# Sheet2.net
KiCad netlist of a schematic drawn in Altium Designer
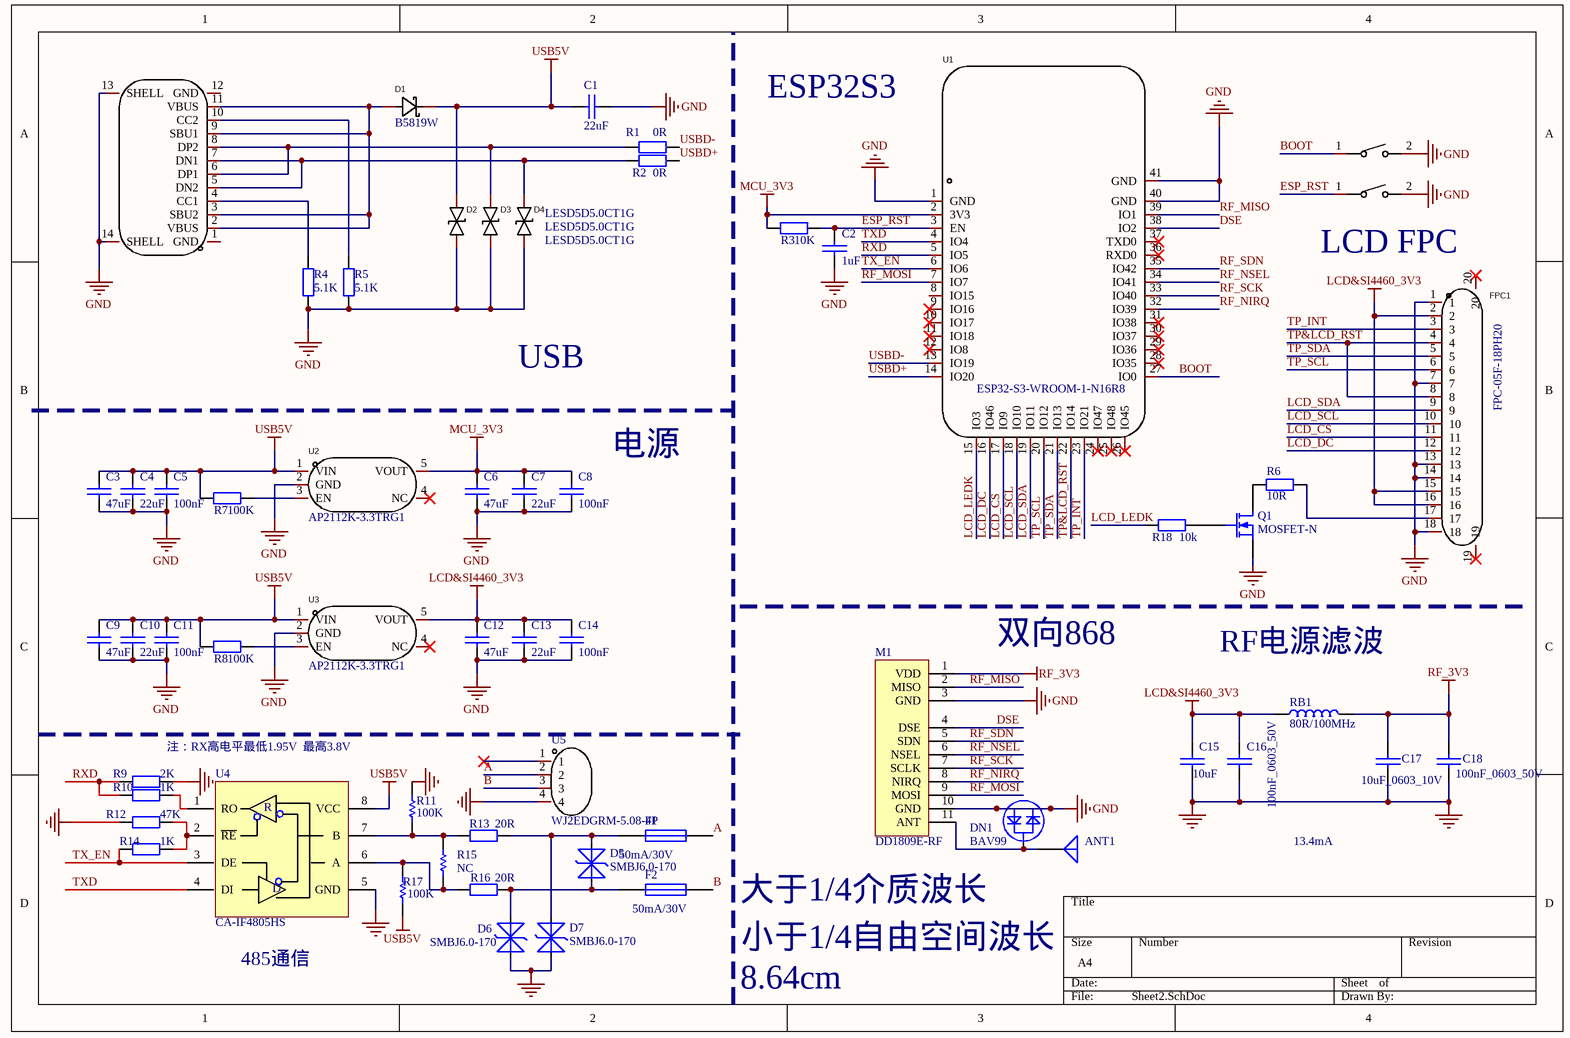
[diagram p0: Sheet2.SchDoc]

(export (version "E")
  (design (tool "Eeschema 10.0.6"))
  (components
    (comp (ref "ANT1")
      (value "~")
      (footprint "18AWG")
      (description "Generic Antenna")
      (fields (field (name "PUBLISHER") "Altium Limited"))
      (libsource (lib "原理图库") (part "Antenna"))
    )
    (comp (ref "C1")
      (value "22uF")
      (footprint "0603_C")
      (description "贴片电容")
      (libsource (lib "Schlib1") (part "CAP_SMT"))
    )
    (comp (ref "C2")
      (value "1uF")
      (footprint "0603_C")
      (description "贴片电容")
      (libsource (lib "Schlib1") (part "CAP_SMT"))
    )
    (comp (ref "C3")
      (value "47uF")
      (footprint "0603_C")
      (description "贴片电容")
      (libsource (lib "Schlib1") (part "CAP_SMT"))
    )
    (comp (ref "C4")
      (value "22uF")
      (footprint "0603_C")
      (description "贴片电容")
      (libsource (lib "Schlib1") (part "CAP_SMT"))
    )
    (comp (ref "C5")
      (value "100nF")
      (footprint "0603_C")
      (description "贴片电容")
      (libsource (lib "Schlib1") (part "CAP_SMT"))
    )
    (comp (ref "C6")
      (value "47uF")
      (footprint "0603_C")
      (description "贴片电容")
      (libsource (lib "Schlib1") (part "CAP_SMT"))
    )
    (comp (ref "C7")
      (value "22uF")
      (footprint "0603_C")
      (description "贴片电容")
      (libsource (lib "Schlib1") (part "CAP_SMT"))
    )
    (comp (ref "C8")
      (value "100nF")
      (footprint "0603_C")
      (description "贴片电容")
      (libsource (lib "Schlib1") (part "CAP_SMT"))
    )
    (comp (ref "C9")
      (value "47uF")
      (footprint "0603_C")
      (description "贴片电容")
      (libsource (lib "Schlib1") (part "CAP_SMT"))
    )
    (comp (ref "C10")
      (value "22uF")
      (footprint "0603_C")
      (description "贴片电容")
      (libsource (lib "Schlib1") (part "CAP_SMT"))
    )
    (comp (ref "C11")
      (value "100nF")
      (footprint "0603_C")
      (description "贴片电容")
      (libsource (lib "Schlib1") (part "CAP_SMT"))
    )
    (comp (ref "C12")
      (value "47uF")
      (footprint "0603_C")
      (description "贴片电容")
      (libsource (lib "Schlib1") (part "CAP_SMT"))
    )
    (comp (ref "C13")
      (value "22uF")
      (footprint "0603_C")
      (description "贴片电容")
      (libsource (lib "Schlib1") (part "CAP_SMT"))
    )
    (comp (ref "C14")
      (value "100nF")
      (footprint "0603_C")
      (description "贴片电容")
      (libsource (lib "Schlib1") (part "CAP_SMT"))
    )
    (comp (ref "C15")
      (value "10uF")
      (footprint "0603_C")
      (description "瓷片电容 X5R-0603-10V-10uF/C-±10%")
      (fields (field (name "Comment") "10uF_0603_10V"))
      (libsource (lib "mine") (part "10uF_0603_10V"))
    )
    (comp (ref "C16")
      (value "100nF_0603_50V")
      (footprint "0603_C")
      (description "电容 瓷片 X7R-0603-50V-0.1uF/C-±10%")
      (libsource (lib "mine") (part "100nF_0603_50V"))
    )
    (comp (ref "C17")
      (value "10uF_0603_10V")
      (footprint "0603_C")
      (description "瓷片电容 X5R-0603-10V-10uF/C-±10%")
      (libsource (lib "mine") (part "10uF_0603_10V"))
    )
    (comp (ref "C18")
      (value "100nF_0603_50V")
      (footprint "0603_C")
      (description "电容 瓷片 X7R-0603-50V-0.1uF/C-±10%")
      (libsource (lib "mine") (part "100nF_0603_50V"))
    )
    (comp (ref "D1")
      (value "B5819W")
      (footprint "SOD-123F_L2.7-W1.6-LS3.8-RD-1")
      (fields (field (name "MANUFACTURER") "GOODWORK(固得沃克)"))
      (libsource (lib "Schlib1") (part "B5819W"))
    )
    (comp (ref "D2")
      (value "LESD5D5.0CT1G")
      (footprint "SOD-523_L1.2-W0.8-LS1.6-BI")
      (fields (field (name "MANUFACTURER") "LRC(乐山无线电)"))
      (libsource (lib "Schlib1") (part "LESD5D5.0CT1G"))
    )
    (comp (ref "D3")
      (value "LESD5D5.0CT1G")
      (footprint "SOD-523_L1.2-W0.8-LS1.6-BI")
      (fields (field (name "MANUFACTURER") "LRC(乐山无线电)"))
      (libsource (lib "Schlib1") (part "LESD5D5.0CT1G"))
    )
    (comp (ref "D4")
      (value "LESD5D5.0CT1G")
      (footprint "SOD-523_L1.2-W0.8-LS1.6-BI")
      (fields (field (name "MANUFACTURER") "LRC(乐山无线电)"))
      (libsource (lib "Schlib1") (part "LESD5D5.0CT1G"))
    )
    (comp (ref "D5")
      (value "SMBJ6.0-170")
      (footprint "SMB(DO-214AA) - TVS")
      (description "TVS")
      (libsource (lib "Schlib1") (part "TVS"))
    )
    (comp (ref "D6")
      (value "SMBJ6.0-170")
      (footprint "SMB(DO-214AA) - TVS")
      (description "TVS")
      (libsource (lib "Schlib1") (part "TVS"))
    )
    (comp (ref "D7")
      (value "SMBJ6.0-170")
      (footprint "SMB(DO-214AA) - TVS")
      (description "TVS")
      (libsource (lib "Schlib1") (part "TVS"))
    )
    (comp (ref "DN1") (value "BAV99") (footprint "SOT-23(SOT-23-3)") (libsource (lib "Ruan") (part "BAV99")))
    (comp (ref "F1")
      (value "贴片自恢复保险丝 1812 0.1A 60V")
      (footprint "1206_R")
      (description "Fuse")
      (fields (field (name "ALTIUM_UNNAMED_1") "50mA/30V") (field (name "PUBLISHER") "Altium Limited"))
      (libsource (lib "*") (part "Fuse 1"))
    )
    (comp (ref "F2")
      (value "贴片自恢复保险丝 1812 0.1A 60V")
      (footprint "1206_R")
      (description "Fuse")
      (fields (field (name "ALTIUM_UNNAMED_1") "50mA/30V") (field (name "PUBLISHER") "Altium Limited"))
      (libsource (lib "*") (part "Fuse 1"))
    )
    (comp (ref "FPC1")
      (value "FPC-05F-18PH20")
      (footprint "FPC-SMD_18P-P0.50_FPC-05F-18PH20")
      (fields (field (name "MANUFACTURER") "XUNPU(讯普)"))
      (libsource (lib "Schlib1") (part "FPC-05F-18PH20"))
    )
    (comp (ref "M1")
      (value "DD1809E-RF")
      (footprint "DD1809(E)-RF-平")
      (description "平插")
      (libsource (lib "Ruan") (part "DD1809E-RF"))
    )
    (comp (ref "Q1")
      (value "MOSFET-N")
      (footprint "SOT-23(SOT-23-3)")
      (description "N-Channel MOSFET")
      (libsource (lib "Schlib1") (part "MOSFET-N"))
    )
    (comp (ref "R1")
      (value "0R")
      (footprint "0603_R")
      (description "Resistor")
      (fields (field (name "PUBLISHER") "Altium Limited"))
      (libsource (lib "Schlib1") (part "RES"))
    )
    (comp (ref "R2")
      (value "0R")
      (footprint "0603_R")
      (description "Resistor")
      (fields (field (name "PUBLISHER") "Altium Limited"))
      (libsource (lib "Schlib1") (part "RES"))
    )
    (comp (ref "R3")
      (value "10K")
      (footprint "0603_R")
      (description "Resistor")
      (fields (field (name "Comment") "0R") (field (name "PUBLISHER") "Altium Limited"))
      (libsource (lib "Schlib1") (part "RES"))
    )
    (comp (ref "R4")
      (value "5.1K")
      (footprint "0603_R")
      (description "Resistor")
      (fields (field (name "PUBLISHER") "Altium Limited"))
      (libsource (lib "") (part "RES_1"))
    )
    (comp (ref "R5")
      (value "5.1K")
      (footprint "0603_R")
      (description "Resistor")
      (fields (field (name "PUBLISHER") "Altium Limited"))
      (libsource (lib "") (part "RES_1"))
    )
    (comp (ref "R6")
      (value "10R")
      (footprint "0603_R")
      (description "Resistor")
      (fields (field (name "Comment") "0R") (field (name "PUBLISHER") "Altium Limited"))
      (libsource (lib "Schlib1") (part "RES"))
    )
    (comp (ref "R7")
      (value "100K")
      (footprint "0603_R")
      (description "Resistor")
      (fields (field (name "PUBLISHER") "Altium Limited"))
      (libsource (lib "Schlib1") (part "RES"))
    )
    (comp (ref "R8")
      (value "100K")
      (footprint "0603_R")
      (description "Resistor")
      (fields (field (name "PUBLISHER") "Altium Limited"))
      (libsource (lib "Schlib1") (part "RES"))
    )
    (comp (ref "R9")
      (value "2K")
      (footprint "0603_R")
      (description "Resistor")
      (fields (field (name "PUBLISHER") "Altium Limited"))
      (libsource (lib "") (part "Res2_2"))
    )
    (comp (ref "R10")
      (value "1K")
      (footprint "0603_R")
      (description "Resistor")
      (fields (field (name "PUBLISHER") "Altium Limited"))
      (libsource (lib "*") (part "Res2"))
    )
    (comp (ref "R11")
      (value "100K")
      (footprint "0603_R")
      (description "Resistor")
      (fields (field (name "PUBLISHER") "Altium Limited"))
      (libsource (lib "*") (part "Res1"))
    )
    (comp (ref "R12")
      (value "47K")
      (footprint "0603_R")
      (description "Resistor")
      (fields (field (name "PUBLISHER") "Altium Limited"))
      (libsource (lib "*") (part "Res2"))
    )
    (comp (ref "R13")
      (value "20R")
      (footprint "0603_R")
      (description "Resistor")
      (fields (field (name "PUBLISHER") "Altium Limited"))
      (libsource (lib "") (part "Res2_1"))
    )
    (comp (ref "R14")
      (value "1K")
      (footprint "0603_R")
      (description "Resistor")
      (fields (field (name "PUBLISHER") "Altium Limited"))
      (libsource (lib "*") (part "Res2"))
    )
    (comp (ref "R15")
      (value "NC")
      (footprint "0603_R")
      (description "Resistor")
      (fields (field (name "PUBLISHER") "Altium Limited"))
      (libsource (lib "*") (part "Res1"))
    )
    (comp (ref "R16")
      (value "20R")
      (footprint "0603_R")
      (description "Resistor")
      (fields (field (name "PUBLISHER") "Altium Limited"))
      (libsource (lib "") (part "Res2_1"))
    )
    (comp (ref "R17")
      (value "100K")
      (footprint "0603_R")
      (description "Resistor")
      (fields (field (name "PUBLISHER") "Altium Limited"))
      (libsource (lib "*") (part "Res1"))
    )
    (comp (ref "R18")
      (value "10k")
      (footprint "0603_R")
      (description "Resistor")
      (fields (field (name "Comment") "0R") (field (name "PUBLISHER") "Altium Limited"))
      (libsource (lib "Schlib1") (part "RES"))
    )
    (comp (ref "RB1")
      (value "80R/100MHz")
      (footprint "0603_R")
      (description "磁珠 80R/100MHZ 贴片0603")
      (fields (field (name "Comment") "80R/100MHz_0603"))
      (libsource (lib "mine") (part "80R/100MHz_0603"))
    )
    (comp (ref "SW1")
      (value "TS-1088-AR02016")
      (footprint "SW-SMD_L3.9-W3.0-P4.45")
      (fields (field (name "MANUFACTURER") "XUNPU(讯普)"))
      (libsource (lib "Schlib1") (part "KEY"))
    )
    (comp (ref "SW2")
      (value "TS-1088-AR02016")
      (footprint "SW-SMD_L3.9-W3.0-P4.45")
      (fields (field (name "MANUFACTURER") "XUNPU(讯普)"))
      (libsource (lib "Schlib1") (part "KEY"))
    )
    (comp (ref "U1")
      (value "ESP32-S3-WROOM-1-N16R8")
      (footprint "WIRELM-SMD_ESP32-S3-WROOM-1")
      (fields (field (name "MANUFACTURER") "ESPRESSIF(乐鑫)"))
      (libsource (lib "Schlib1") (part "ESP32-S3-WROOM-1-N16R8"))
    )
    (comp (ref "U2")
      (value "AP2112K-3.3TRG1")
      (footprint "SOT-25-5_L2.9-W1.6-P0.95-LS2.8-BL")
      (fields (field (name "MANUFACTURER") "DIODES(美台)"))
      (libsource (lib "Schlib1") (part "AP2112K-3.3TRG1"))
    )
    (comp (ref "U3")
      (value "AP2112K-3.3TRG1")
      (footprint "SOT-25-5_L2.9-W1.6-P0.95-LS2.8-BL")
      (fields (field (name "MANUFACTURER") "DIODES(美台)"))
      (libsource (lib "Schlib1") (part "AP2112K-3.3TRG1"))
    )
    (comp (ref "U4")
      (value "CA-IF4805HS")
      (footprint "SOP8")
      (description "MAX485E")
      (libsource (lib "N IC-GRC") (part "MAX485E"))
    )
    (comp (ref "U5")
      (value "WJ2EDGRM-5.08-4P")
      (footprint "CONN-TH_4P-P5.08_WJ2EDGRM-5.08-4P-14-00A")
      (description "连接器类型:板端/插座-闭口;间距:5.08mm;排数:1;每排PIN数:4;安装方式:弯针;颜色:绿色;固定方式:螺丝固定;")
      (fields (field (name "MANUFACTURER") "KANGNEX(康奈克斯电气)") (field (name "NAME") "WJ2EDGRM-5.08-4P"))
      (libsource (lib "Schlib1") (part "WJ2EDGRM-5.08-4P"))
    )
    (comp (ref "USB1")
      (value "TYPE-C 16PIN 2MD(073)")
      (footprint "USB-C-SMD_TYPE-C-6PIN-2MD-073")
      (fields (field (name "MANUFACTURER") "SHOU HAN(首韩)"))
      (libsource (lib "Schlib1") (part "TYPE-C 16PIN 2MD(073)"))
    )
  )
  (nets
    (net (code "1") (name "/A") (class "Default")
      (node (ref "F1") (pin "2") (pinfunction "2_2") (pintype "passive"))
      (node (ref "U5") (pin "2") (pinfunction "2_2") (pintype "passive"))
    )
    (net (code "2") (name "/B") (class "Default")
      (node (ref "F2") (pin "2") (pinfunction "2_2") (pintype "passive"))
      (node (ref "U5") (pin "3") (pinfunction "3_3") (pintype "passive"))
    )
    (net (code "3") (name "/BOOT") (class "Default")
      (node (ref "SW1") (pin "1") (pinfunction "1_1") (pintype "passive"))
      (node (ref "U1") (pin "27") (pinfunction "IO0_27") (pintype "passive"))
    )
    (net (code "4") (name "/DSE") (class "Default")
      (node (ref "M1") (pin "4") (pinfunction "DSE_4") (pintype "passive"))
      (node (ref "U1") (pin "38") (pinfunction "IO2_38") (pintype "passive"))
    )
    (net (code "5") (name "/ESP_RST") (class "Default")
      (node (ref "C2") (pin "2") (pinfunction "2_2") (pintype "passive"))
      (node (ref "R3") (pin "2") (pinfunction "2_2") (pintype "passive"))
      (node (ref "SW2") (pin "1") (pinfunction "1_1") (pintype "passive"))
      (node (ref "U1") (pin "3") (pinfunction "EN_3") (pintype "passive"))
    )
    (net (code "6") (name "/LCD_CS") (class "Default")
      (node (ref "FPC1") (pin "11") (pinfunction "11_11") (pintype "passive"))
      (node (ref "U1") (pin "17") (pinfunction "IO9_17") (pintype "passive"))
    )
    (net (code "7") (name "/LCD_DC") (class "Default")
      (node (ref "FPC1") (pin "12") (pinfunction "12_12") (pintype "passive"))
      (node (ref "U1") (pin "16") (pinfunction "IO46_16") (pintype "passive"))
    )
    (net (code "8") (name "/LCD_LEDK") (class "Default")
      (node (ref "R18") (pin "1") (pinfunction "1_1") (pintype "passive"))
      (node (ref "U1") (pin "15") (pinfunction "IO3_15") (pintype "passive"))
    )
    (net (code "9") (name "/LCD_SCL") (class "Default")
      (node (ref "FPC1") (pin "10") (pinfunction "10_10") (pintype "passive"))
      (node (ref "U1") (pin "18") (pinfunction "IO10_18") (pintype "passive"))
    )
    (net (code "10") (name "/LCD_SDA") (class "Default")
      (node (ref "FPC1") (pin "9") (pinfunction "9_9") (pintype "passive"))
      (node (ref "U1") (pin "19") (pinfunction "IO11_19") (pintype "passive"))
    )
    (net (code "11") (name "/RF_MISO") (class "Default")
      (node (ref "M1") (pin "2") (pinfunction "MISO_2") (pintype "passive"))
      (node (ref "U1") (pin "39") (pinfunction "IO1_39") (pintype "passive"))
    )
    (net (code "12") (name "/RF_MOSI") (class "Default")
      (node (ref "M1") (pin "9") (pinfunction "MOSI_9") (pintype "passive"))
      (node (ref "U1") (pin "7") (pinfunction "IO7_7") (pintype "passive"))
    )
    (net (code "13") (name "/RF_NIRQ") (class "Default")
      (node (ref "M1") (pin "8") (pinfunction "NIRQ_8") (pintype "passive"))
      (node (ref "U1") (pin "32") (pinfunction "IO39_32") (pintype "passive"))
    )
    (net (code "14") (name "/RF_NSEL") (class "Default")
      (node (ref "M1") (pin "6") (pinfunction "NSEL_6") (pintype "passive"))
      (node (ref "U1") (pin "34") (pinfunction "IO41_34") (pintype "passive"))
    )
    (net (code "15") (name "/RF_SCK") (class "Default")
      (node (ref "M1") (pin "7") (pinfunction "SCLK_7") (pintype "passive"))
      (node (ref "U1") (pin "33") (pinfunction "IO40_33") (pintype "passive"))
    )
    (net (code "16") (name "/RF_SDN") (class "Default")
      (node (ref "M1") (pin "5") (pinfunction "SDN_5") (pintype "passive"))
      (node (ref "U1") (pin "35") (pinfunction "IO42_35") (pintype "passive"))
    )
    (net (code "17") (name "/RXD") (class "Default")
      (node (ref "R10") (pin "1") (pinfunction "1_1") (pintype "passive"))
      (node (ref "R9") (pin "2") (pinfunction "2_2") (pintype "passive"))
      (node (ref "U1") (pin "5") (pinfunction "IO5_5") (pintype "passive"))
    )
    (net (code "18") (name "/TP&LCD_RST") (class "Default")
      (node (ref "FPC1") (pin "4") (pinfunction "4_4") (pintype "passive"))
      (node (ref "FPC1") (pin "8") (pinfunction "8_8") (pintype "passive"))
      (node (ref "U1") (pin "22") (pinfunction "IO14_22") (pintype "passive"))
    )
    (net (code "19") (name "/TP_INT") (class "Default")
      (node (ref "FPC1") (pin "3") (pinfunction "3_3") (pintype "passive"))
      (node (ref "U1") (pin "23") (pinfunction "IO21_23") (pintype "passive"))
    )
    (net (code "20") (name "/TP_SCL") (class "Default")
      (node (ref "FPC1") (pin "6") (pinfunction "6_6") (pintype "passive"))
      (node (ref "U1") (pin "20") (pinfunction "IO12_20") (pintype "passive"))
    )
    (net (code "21") (name "/TP_SDA") (class "Default")
      (node (ref "FPC1") (pin "5") (pinfunction "5_5") (pintype "passive"))
      (node (ref "U1") (pin "21") (pinfunction "IO13_21") (pintype "passive"))
    )
    (net (code "22") (name "/TXD") (class "Default")
      (node (ref "U1") (pin "4") (pinfunction "IO4_4") (pintype "passive"))
      (node (ref "U4") (pin "4") (pinfunction "DI_4") (pintype "passive"))
    )
    (net (code "23") (name "/TX_EN") (class "Default")
      (node (ref "R14") (pin "1") (pinfunction "1_1") (pintype "passive"))
      (node (ref "U1") (pin "6") (pinfunction "IO6_6") (pintype "passive"))
      (node (ref "U4") (pin "3") (pinfunction "DE_3") (pintype "passive"))
    )
    (net (code "24") (name "/USBD+") (class "Default")
      (node (ref "R2") (pin "2") (pinfunction "2_2") (pintype "passive"))
      (node (ref "U1") (pin "14") (pinfunction "IO20_14") (pintype "passive"))
    )
    (net (code "25") (name "/USBD-") (class "Default")
      (node (ref "R1") (pin "2") (pinfunction "2_2") (pintype "passive"))
      (node (ref "U1") (pin "13") (pinfunction "IO19_13") (pintype "passive"))
    )
    (net (code "26") (name "GND") (class "Default")
      (node (ref "C1") (pin "2") (pinfunction "2_2") (pintype "passive"))
      (node (ref "C10") (pin "1") (pinfunction "1_1") (pintype "passive"))
      (node (ref "C11") (pin "1") (pinfunction "1_1") (pintype "passive"))
      (node (ref "C12") (pin "1") (pinfunction "1_1") (pintype "passive"))
      (node (ref "C13") (pin "1") (pinfunction "1_1") (pintype "passive"))
      (node (ref "C14") (pin "1") (pinfunction "1_1") (pintype "passive"))
      (node (ref "C15") (pin "2") (pinfunction "2_2") (pintype "passive"))
      (node (ref "C16") (pin "1") (pinfunction "1_1") (pintype "passive"))
      (node (ref "C17") (pin "1") (pinfunction "1_1") (pintype "passive"))
      (node (ref "C18") (pin "1") (pinfunction "1_1") (pintype "passive"))
      (node (ref "C2") (pin "1") (pinfunction "1_1") (pintype "passive"))
      (node (ref "C3") (pin "1") (pinfunction "1_1") (pintype "passive"))
      (node (ref "C4") (pin "1") (pinfunction "1_1") (pintype "passive"))
      (node (ref "C5") (pin "1") (pinfunction "1_1") (pintype "passive"))
      (node (ref "C6") (pin "1") (pinfunction "1_1") (pintype "passive"))
      (node (ref "C7") (pin "1") (pinfunction "1_1") (pintype "passive"))
      (node (ref "C8") (pin "1") (pinfunction "1_1") (pintype "passive"))
      (node (ref "C9") (pin "1") (pinfunction "1_1") (pintype "passive"))
      (node (ref "D2") (pin "1") (pinfunction "1_1") (pintype "passive"))
      (node (ref "D3") (pin "1") (pinfunction "1_1") (pintype "passive"))
      (node (ref "D4") (pin "1") (pinfunction "1_1") (pintype "passive"))
      (node (ref "D6") (pin "1") (pinfunction "1_1") (pintype "passive"))
      (node (ref "D7") (pin "1") (pinfunction "1_1") (pintype "passive"))
      (node (ref "DN1") (pin "1") (pinfunction "1_1") (pintype "passive"))
      (node (ref "DN1") (pin "2") (pinfunction "2_2") (pintype "passive"))
      (node (ref "FPC1") (pin "1") (pinfunction "1_1") (pintype "passive"))
      (node (ref "FPC1") (pin "13") (pinfunction "13_13") (pintype "passive"))
      (node (ref "FPC1") (pin "14") (pinfunction "14_14") (pintype "passive"))
      (node (ref "FPC1") (pin "18") (pinfunction "18_18") (pintype "passive"))
      (node (ref "FPC1") (pin "7") (pinfunction "7_7") (pintype "passive"))
      (node (ref "M1") (pin "10") (pinfunction "GND_10") (pintype "passive"))
      (node (ref "M1") (pin "3") (pinfunction "GND_3") (pintype "passive"))
      (node (ref "Q1") (pin "2") (pinfunction "S_2") (pintype "passive"))
      (node (ref "R11") (pin "2") (pinfunction "2_2") (pintype "passive"))
      (node (ref "R12") (pin "1") (pinfunction "1_1") (pintype "passive"))
      (node (ref "R4") (pin "1") (pinfunction "1_1") (pintype "passive"))
      (node (ref "R5") (pin "1") (pinfunction "1_1") (pintype "passive"))
      (node (ref "R9") (pin "1") (pinfunction "1_1") (pintype "passive"))
      (node (ref "SW1") (pin "2") (pinfunction "2_2") (pintype "passive"))
      (node (ref "SW2") (pin "2") (pinfunction "2_2") (pintype "passive"))
      (node (ref "U1") (pin "1") (pinfunction "GND_1") (pintype "passive"))
      (node (ref "U1") (pin "40") (pinfunction "GND_40") (pintype "passive"))
      (node (ref "U1") (pin "41") (pinfunction "GND_41") (pintype "passive"))
      (node (ref "U2") (pin "2") (pinfunction "GND_2") (pintype "passive"))
      (node (ref "U3") (pin "2") (pinfunction "GND_2") (pintype "passive"))
      (node (ref "U4") (pin "5") (pinfunction "GND_5") (pintype "passive"))
      (node (ref "U5") (pin "4") (pinfunction "4_4") (pintype "passive"))
      (node (ref "USB1") (pin "13") (pinfunction "SHELL_13") (pintype "passive"))
      (node (ref "USB1") (pin "14") (pinfunction "SHELL_14") (pintype "passive"))
    )
    (net (code "27") (name "LCD&SI4460_3V3") (class "Default")
      (node (ref "C12") (pin "2") (pinfunction "2_2") (pintype "passive"))
      (node (ref "C13") (pin "2") (pinfunction "2_2") (pintype "passive"))
      (node (ref "C14") (pin "2") (pinfunction "2_2") (pintype "passive"))
      (node (ref "C15") (pin "1") (pinfunction "1_1") (pintype "passive"))
      (node (ref "C16") (pin "2") (pinfunction "2_2") (pintype "passive"))
      (node (ref "FPC1") (pin "15") (pinfunction "15_15") (pintype "passive"))
      (node (ref "FPC1") (pin "16") (pinfunction "16_16") (pintype "passive"))
      (node (ref "FPC1") (pin "2") (pinfunction "2_2") (pintype "passive"))
      (node (ref "RB1") (pin "1") (pinfunction "1_1") (pintype "passive"))
      (node (ref "U3") (pin "5") (pinfunction "VOUT_5") (pintype "passive"))
    )
    (net (code "28") (name "MCU_3V3") (class "Default")
      (node (ref "C6") (pin "2") (pinfunction "2_2") (pintype "passive"))
      (node (ref "C7") (pin "2") (pinfunction "2_2") (pintype "passive"))
      (node (ref "C8") (pin "2") (pinfunction "2_2") (pintype "passive"))
      (node (ref "R3") (pin "1") (pinfunction "1_1") (pintype "passive"))
      (node (ref "U1") (pin "2") (pinfunction "3V3_2") (pintype "passive"))
      (node (ref "U2") (pin "5") (pinfunction "VOUT_5") (pintype "passive"))
    )
    (net (code "29") (name "Net-(ANT1-A)") (class "Default")
      (node (ref "ANT1") (pin "1") (pinfunction "A_1") (pintype "passive"))
      (node (ref "DN1") (pin "3") (pinfunction "3_3") (pintype "passive"))
      (node (ref "M1") (pin "11") (pinfunction "ANT_11") (pintype "passive"))
    )
    (net (code "30") (name "Net-(D1-A)") (class "Default")
      (node (ref "D1") (pin "2") (pinfunction "A_2") (pintype "passive"))
      (node (ref "USB1") (pin "11") (pinfunction "VBUS_11") (pintype "passive"))
      (node (ref "USB1") (pin "2") (pinfunction "VBUS_2") (pintype "passive"))
      (node (ref "USB1") (pin "3") (pinfunction "SBU2_3") (pintype "passive"))
      (node (ref "USB1") (pin "9") (pinfunction "SBU1_9") (pintype "passive"))
    )
    (net (code "31") (name "Net-(D5-Pad1)") (class "Default")
      (node (ref "D5") (pin "1") (pinfunction "1_1") (pintype "passive"))
      (node (ref "D6") (pin "2") (pinfunction "2_2") (pintype "passive"))
      (node (ref "F2") (pin "1") (pinfunction "1_1") (pintype "passive"))
      (node (ref "R16") (pin "1") (pinfunction "1_1") (pintype "passive"))
    )
    (net (code "32") (name "Net-(D5-Pad2)") (class "Default")
      (node (ref "D5") (pin "2") (pinfunction "2_2") (pintype "passive"))
      (node (ref "D7") (pin "2") (pinfunction "2_2") (pintype "passive"))
      (node (ref "F1") (pin "1") (pinfunction "1_1") (pintype "passive"))
      (node (ref "R13") (pin "1") (pinfunction "1_1") (pintype "passive"))
    )
    (net (code "33") (name "Net-(FPC1-Pad17)") (class "Default")
      (node (ref "FPC1") (pin "17") (pinfunction "17_17") (pintype "passive"))
      (node (ref "R6") (pin "2") (pinfunction "2_2") (pintype "passive"))
    )
    (net (code "34") (name "Net-(Q1-D)") (class "Default")
      (node (ref "Q1") (pin "3") (pinfunction "D_3") (pintype "passive"))
      (node (ref "R6") (pin "1") (pinfunction "1_1") (pintype "passive"))
    )
    (net (code "35") (name "Net-(Q1-G)") (class "Default")
      (node (ref "Q1") (pin "1") (pinfunction "G_1") (pintype "passive"))
      (node (ref "R18") (pin "2") (pinfunction "2_2") (pintype "passive"))
    )
    (net (code "36") (name "Net-(U2-EN)") (class "Default")
      (node (ref "R7") (pin "2") (pinfunction "2_2") (pintype "passive"))
      (node (ref "U2") (pin "3") (pinfunction "EN_3") (pintype "passive"))
    )
    (net (code "37") (name "Net-(U3-EN)") (class "Default")
      (node (ref "R8") (pin "2") (pinfunction "2_2") (pintype "passive"))
      (node (ref "U3") (pin "3") (pinfunction "EN_3") (pintype "passive"))
    )
    (net (code "38") (name "Net-(U4-A)") (class "Default")
      (node (ref "R15") (pin "1") (pinfunction "1_1") (pintype "passive"))
      (node (ref "R16") (pin "2") (pinfunction "2_2") (pintype "passive"))
      (node (ref "R17") (pin "2") (pinfunction "2_2") (pintype "passive"))
      (node (ref "U4") (pin "6") (pinfunction "A_6") (pintype "passive"))
    )
    (net (code "39") (name "Net-(U4-B)") (class "Default")
      (node (ref "R11") (pin "1") (pinfunction "1_1") (pintype "passive"))
      (node (ref "R13") (pin "2") (pinfunction "2_2") (pintype "passive"))
      (node (ref "R15") (pin "2") (pinfunction "2_2") (pintype "passive"))
      (node (ref "U4") (pin "7") (pinfunction "B_7") (pintype "passive"))
    )
    (net (code "40") (name "Net-(U4-RO)") (class "Default")
      (node (ref "R10") (pin "2") (pinfunction "2_2") (pintype "passive"))
      (node (ref "U4") (pin "1") (pinfunction "RO_1") (pintype "passive"))
    )
    (net (code "41") (name "Net-(U4-~{RE})") (class "Default")
      (node (ref "R12") (pin "2") (pinfunction "2_2") (pintype "passive"))
      (node (ref "R14") (pin "2") (pinfunction "2_2") (pintype "passive"))
      (node (ref "U4") (pin "2") (pinfunction "~{RE}_2") (pintype "passive"))
    )
    (net (code "42") (name "Net-(USB1-CC1)") (class "Default")
      (node (ref "R4") (pin "2") (pinfunction "2_2") (pintype "passive"))
      (node (ref "USB1") (pin "4") (pinfunction "CC1_4") (pintype "passive"))
    )
    (net (code "43") (name "Net-(USB1-CC2)") (class "Default")
      (node (ref "R5") (pin "2") (pinfunction "2_2") (pintype "passive"))
      (node (ref "USB1") (pin "10") (pinfunction "CC2_10") (pintype "passive"))
    )
    (net (code "44") (name "Net-(USB1-DN1)") (class "Default")
      (node (ref "D4") (pin "2") (pinfunction "2_2") (pintype "passive"))
      (node (ref "R2") (pin "1") (pinfunction "1_1") (pintype "passive"))
      (node (ref "USB1") (pin "5") (pinfunction "DN2_5") (pintype "passive"))
      (node (ref "USB1") (pin "7") (pinfunction "DN1_7") (pintype "passive"))
    )
    (net (code "45") (name "Net-(USB1-DP1)") (class "Default")
      (node (ref "D3") (pin "2") (pinfunction "2_2") (pintype "passive"))
      (node (ref "R1") (pin "1") (pinfunction "1_1") (pintype "passive"))
      (node (ref "USB1") (pin "6") (pinfunction "DP1_6") (pintype "passive"))
      (node (ref "USB1") (pin "8") (pinfunction "DP2_8") (pintype "passive"))
    )
    (net (code "46") (name "RF_3V3") (class "Default")
      (node (ref "C17") (pin "2") (pinfunction "2_2") (pintype "passive"))
      (node (ref "C18") (pin "2") (pinfunction "2_2") (pintype "passive"))
      (node (ref "M1") (pin "1") (pinfunction "VDD_1") (pintype "passive"))
      (node (ref "RB1") (pin "2") (pinfunction "2_2") (pintype "passive"))
    )
    (net (code "47") (name "USB5V") (class "Default")
      (node (ref "C1") (pin "1") (pinfunction "1_1") (pintype "passive"))
      (node (ref "C10") (pin "2") (pinfunction "2_2") (pintype "passive"))
      (node (ref "C11") (pin "2") (pinfunction "2_2") (pintype "passive"))
      (node (ref "C3") (pin "2") (pinfunction "2_2") (pintype "passive"))
      (node (ref "C4") (pin "2") (pinfunction "2_2") (pintype "passive"))
      (node (ref "C5") (pin "2") (pinfunction "2_2") (pintype "passive"))
      (node (ref "C9") (pin "2") (pinfunction "2_2") (pintype "passive"))
      (node (ref "D1") (pin "1") (pinfunction "K_1") (pintype "passive"))
      (node (ref "D2") (pin "2") (pinfunction "2_2") (pintype "passive"))
      (node (ref "R17") (pin "1") (pinfunction "1_1") (pintype "passive"))
      (node (ref "R7") (pin "1") (pinfunction "1_1") (pintype "passive"))
      (node (ref "R8") (pin "1") (pinfunction "1_1") (pintype "passive"))
      (node (ref "U2") (pin "1") (pinfunction "VIN_1") (pintype "passive"))
      (node (ref "U3") (pin "1") (pinfunction "VIN_1") (pintype "passive"))
      (node (ref "U4") (pin "8") (pinfunction "VCC_8") (pintype "passive"))
    )
    (net (code "48") (name "unconnected-(FPC1-Pad19)") (class "Default")
      (node (ref "FPC1") (pin "19") (pinfunction "19_19") (pintype "passive+no_connect"))
    )
    (net (code "49") (name "unconnected-(FPC1-Pad20)") (class "Default")
      (node (ref "FPC1") (pin "20") (pinfunction "20_20") (pintype "passive+no_connect"))
    )
    (net (code "50") (name "unconnected-(U1-IO8-Pad12)") (class "Default")
      (node (ref "U1") (pin "12") (pinfunction "IO8_12") (pintype "passive+no_connect"))
    )
    (net (code "51") (name "unconnected-(U1-IO15-Pad8)") (class "Default")
      (node (ref "U1") (pin "8") (pinfunction "IO15_8") (pintype "passive"))
    )
    (net (code "52") (name "unconnected-(U1-IO16-Pad9)") (class "Default")
      (node (ref "U1") (pin "9") (pinfunction "IO16_9") (pintype "passive+no_connect"))
    )
    (net (code "53") (name "unconnected-(U1-IO17-Pad10)") (class "Default")
      (node (ref "U1") (pin "10") (pinfunction "IO17_10") (pintype "passive+no_connect"))
    )
    (net (code "54") (name "unconnected-(U1-IO18-Pad11)") (class "Default")
      (node (ref "U1") (pin "11") (pinfunction "IO18_11") (pintype "passive+no_connect"))
    )
    (net (code "55") (name "unconnected-(U1-IO35-Pad28)") (class "Default")
      (node (ref "U1") (pin "28") (pinfunction "IO35_28") (pintype "passive+no_connect"))
    )
    (net (code "56") (name "unconnected-(U1-IO36-Pad29)") (class "Default")
      (node (ref "U1") (pin "29") (pinfunction "IO36_29") (pintype "passive+no_connect"))
    )
    (net (code "57") (name "unconnected-(U1-IO37-Pad30)") (class "Default")
      (node (ref "U1") (pin "30") (pinfunction "IO37_30") (pintype "passive+no_connect"))
    )
    (net (code "58") (name "unconnected-(U1-IO38-Pad31)") (class "Default")
      (node (ref "U1") (pin "31") (pinfunction "IO38_31") (pintype "passive+no_connect"))
    )
    (net (code "59") (name "unconnected-(U1-IO45-Pad26)") (class "Default")
      (node (ref "U1") (pin "26") (pinfunction "IO45_26") (pintype "passive+no_connect"))
    )
    (net (code "60") (name "unconnected-(U1-IO47-Pad24)") (class "Default")
      (node (ref "U1") (pin "24") (pinfunction "IO47_24") (pintype "passive+no_connect"))
    )
    (net (code "61") (name "unconnected-(U1-IO48-Pad25)") (class "Default")
      (node (ref "U1") (pin "25") (pinfunction "IO48_25") (pintype "passive+no_connect"))
    )
    (net (code "62") (name "unconnected-(U1-RXD0-Pad36)") (class "Default")
      (node (ref "U1") (pin "36") (pinfunction "RXD0_36") (pintype "passive+no_connect"))
    )
    (net (code "63") (name "unconnected-(U1-TXD0-Pad37)") (class "Default")
      (node (ref "U1") (pin "37") (pinfunction "TXD0_37") (pintype "passive+no_connect"))
    )
    (net (code "64") (name "unconnected-(U2-NC-Pad4)") (class "Default")
      (node (ref "U2") (pin "4") (pinfunction "NC_4") (pintype "passive+no_connect"))
    )
    (net (code "65") (name "unconnected-(U3-NC-Pad4)") (class "Default")
      (node (ref "U3") (pin "4") (pinfunction "NC_4") (pintype "passive+no_connect"))
    )
    (net (code "66") (name "unconnected-(U5-Pad1)") (class "Default")
      (node (ref "U5") (pin "1") (pinfunction "1_1") (pintype "passive+no_connect"))
    )
    (net (code "67") (name "unconnected-(USB1-GND-Pad1)") (class "Default")
      (node (ref "USB1") (pin "1") (pinfunction "GND_1") (pintype "passive"))
    )
    (net (code "68") (name "unconnected-(USB1-GND-Pad12)") (class "Default")
      (node (ref "USB1") (pin "12") (pinfunction "GND_12") (pintype "passive"))
    )
  )
)
